# mcu_v2_0_sch.net
KiCad netlist of a schematic drawn in EAGLE
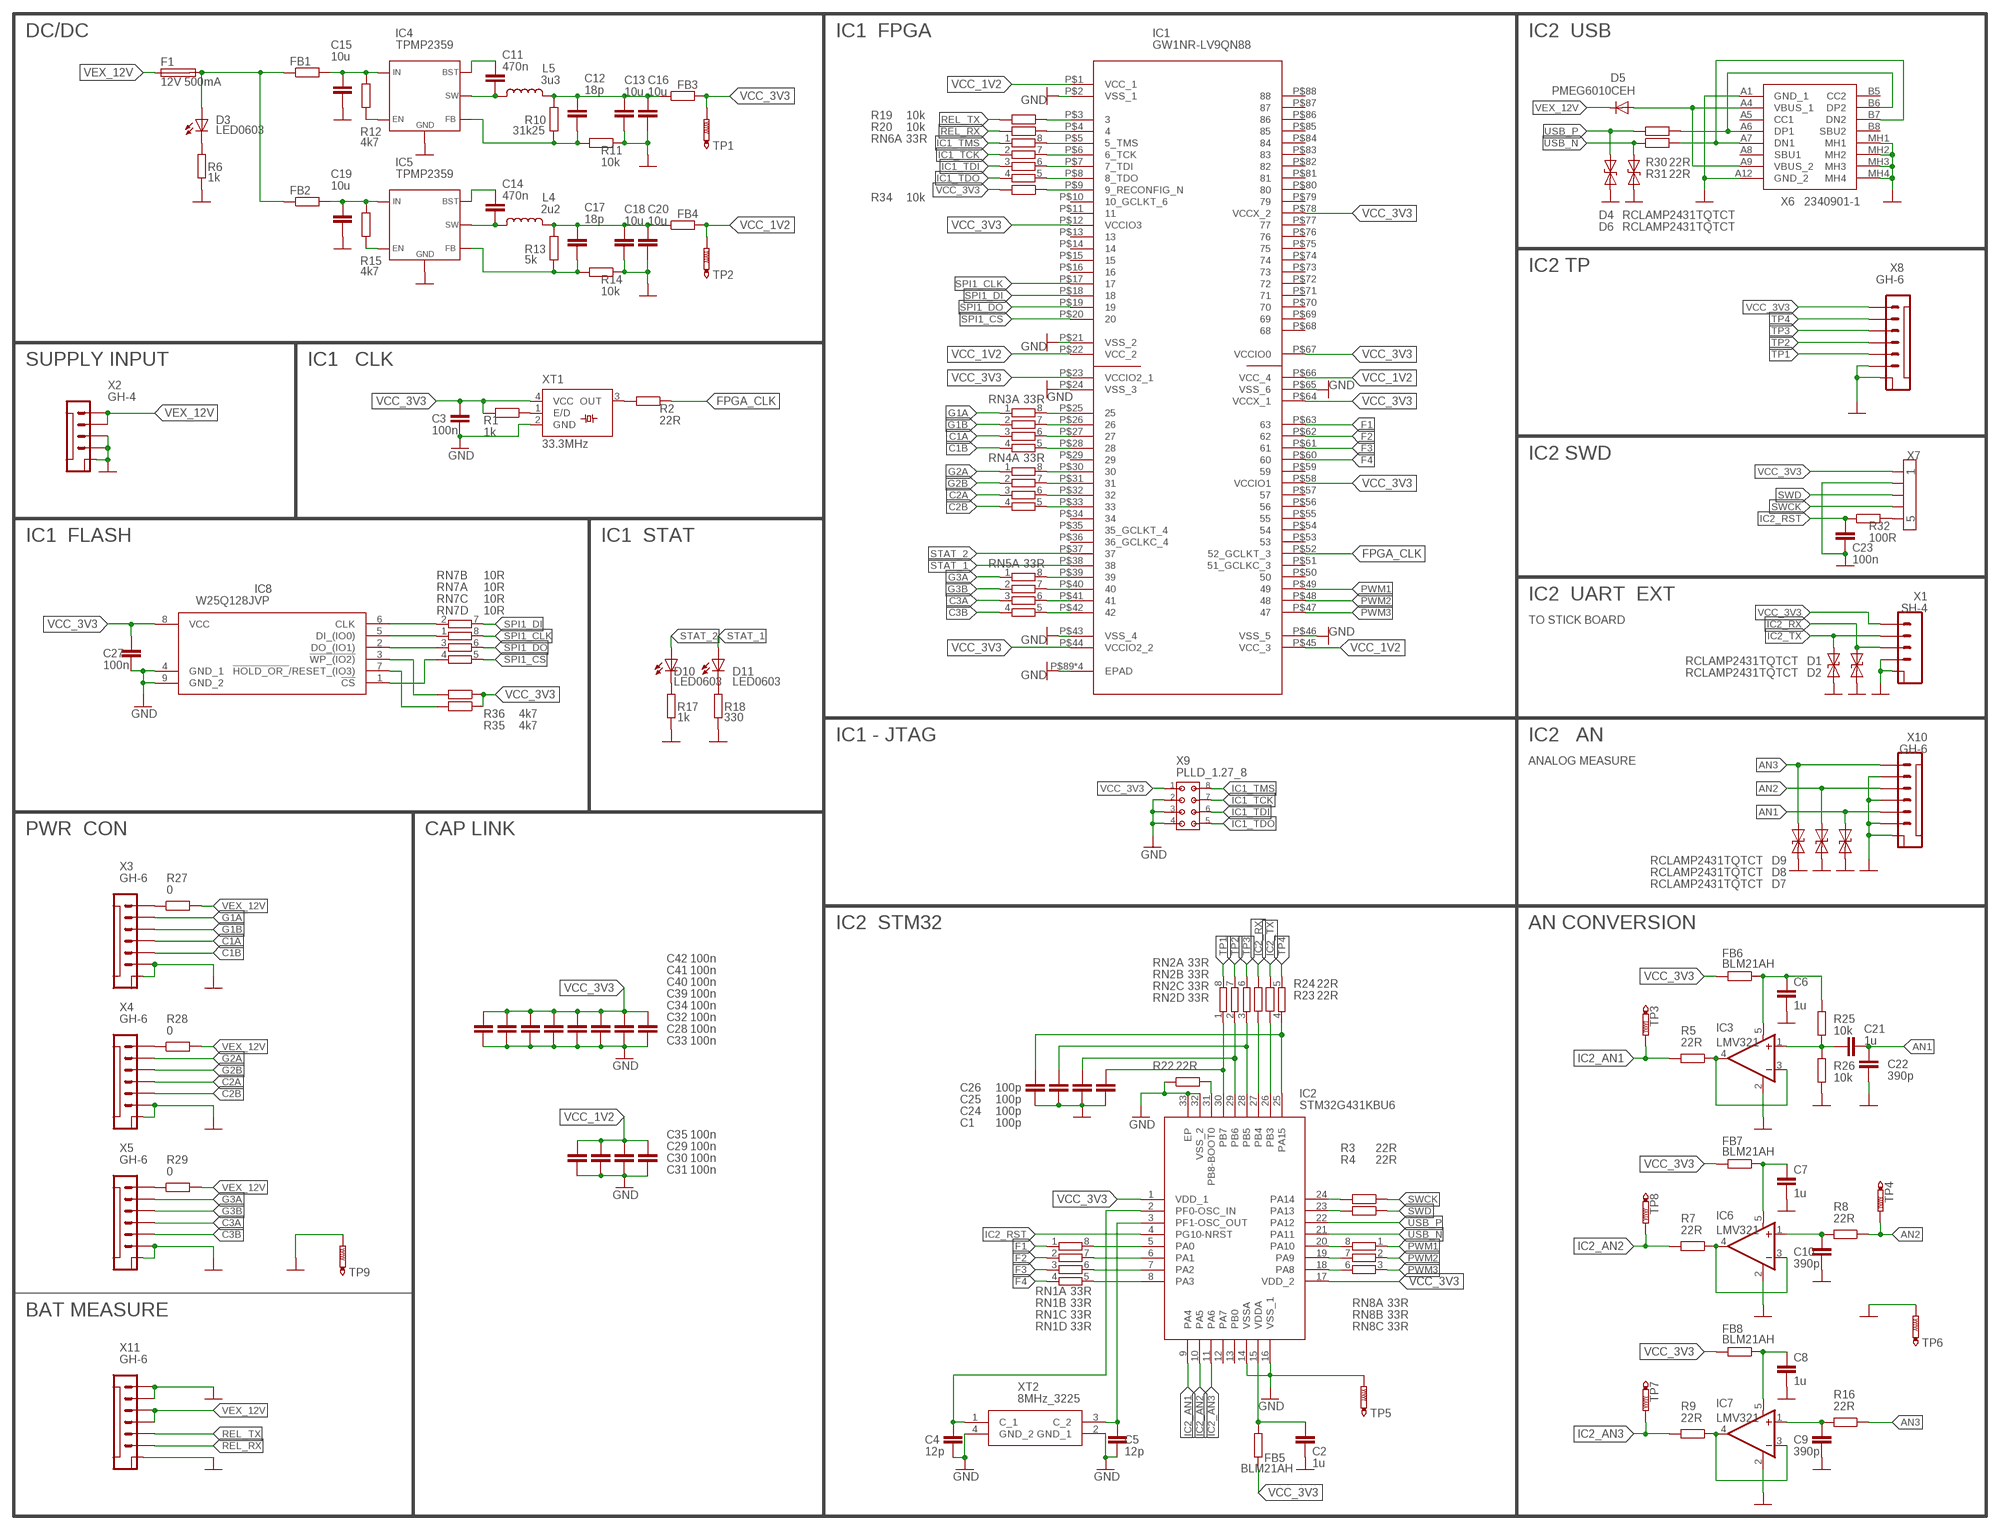
[diagram p0: schematic, sheet 1]

(export (version "E")
  (design (tool "Eeschema 10.0.6"))
  (components
    (comp (ref "C1")
      (value "100p")
      (footprint "eagle-import:C0402")
      (libsource (lib "eagle-import") (part "C-EUC0402"))
    )
    (comp (ref "C2")
      (value "1u")
      (footprint "eagle-import:C0603")
      (libsource (lib "eagle-import") (part "C-EUC0603"))
    )
    (comp (ref "C3")
      (value "100n")
      (footprint "eagle-import:C0603")
      (libsource (lib "eagle-import") (part "C-EUC0603"))
    )
    (comp (ref "C4")
      (value "12p")
      (footprint "eagle-import:C0603")
      (libsource (lib "eagle-import") (part "C-EUC0603"))
    )
    (comp (ref "C5")
      (value "12p")
      (footprint "eagle-import:C0603")
      (libsource (lib "eagle-import") (part "C-EUC0603"))
    )
    (comp (ref "C6")
      (value "1u")
      (footprint "eagle-import:C0603")
      (libsource (lib "eagle-import") (part "C-EUC0603"))
    )
    (comp (ref "C7")
      (value "1u")
      (footprint "eagle-import:C0603")
      (libsource (lib "eagle-import") (part "C-EUC0603"))
    )
    (comp (ref "C8")
      (value "1u")
      (footprint "eagle-import:C0603")
      (libsource (lib "eagle-import") (part "C-EUC0603"))
    )
    (comp (ref "C9")
      (value "390p")
      (footprint "eagle-import:C0603")
      (libsource (lib "eagle-import") (part "C-EUC0603"))
    )
    (comp (ref "C10")
      (value "390p")
      (footprint "eagle-import:C0603")
      (libsource (lib "eagle-import") (part "C-EUC0603"))
    )
    (comp (ref "C11")
      (value "470n")
      (footprint "eagle-import:C0603")
      (libsource (lib "eagle-import") (part "C-EUC0603"))
    )
    (comp (ref "C12")
      (value "18p")
      (footprint "eagle-import:C0603")
      (libsource (lib "eagle-import") (part "C-EUC0603"))
    )
    (comp (ref "C13")
      (value "10u")
      (footprint "eagle-import:C0805")
      (libsource (lib "eagle-import") (part "C-EUC0805"))
    )
    (comp (ref "C14")
      (value "470n")
      (footprint "eagle-import:C0603")
      (libsource (lib "eagle-import") (part "C-EUC0603"))
    )
    (comp (ref "C15")
      (value "10u")
      (footprint "eagle-import:C0805")
      (libsource (lib "eagle-import") (part "C-EUC0805"))
    )
    (comp (ref "C16")
      (value "10u")
      (footprint "eagle-import:C0805")
      (libsource (lib "eagle-import") (part "C-EUC0805"))
    )
    (comp (ref "C17")
      (value "18p")
      (footprint "eagle-import:C0603")
      (libsource (lib "eagle-import") (part "C-EUC0603"))
    )
    (comp (ref "C18")
      (value "10u")
      (footprint "eagle-import:C0805")
      (libsource (lib "eagle-import") (part "C-EUC0805"))
    )
    (comp (ref "C19")
      (value "10u")
      (footprint "eagle-import:C0805")
      (libsource (lib "eagle-import") (part "C-EUC0805"))
    )
    (comp (ref "C20")
      (value "10u")
      (footprint "eagle-import:C0805")
      (libsource (lib "eagle-import") (part "C-EUC0805"))
    )
    (comp (ref "C21")
      (value "1u")
      (footprint "eagle-import:C0603")
      (libsource (lib "eagle-import") (part "C-EUC0603"))
    )
    (comp (ref "C22")
      (value "390p")
      (footprint "eagle-import:C0603")
      (libsource (lib "eagle-import") (part "C-EUC0603"))
    )
    (comp (ref "C23")
      (value "100n")
      (footprint "eagle-import:C0402")
      (libsource (lib "eagle-import") (part "C-EUC0402"))
    )
    (comp (ref "C24")
      (value "100p")
      (footprint "eagle-import:C0402")
      (libsource (lib "eagle-import") (part "C-EUC0402"))
    )
    (comp (ref "C25")
      (value "100p")
      (footprint "eagle-import:C0402")
      (libsource (lib "eagle-import") (part "C-EUC0402"))
    )
    (comp (ref "C26")
      (value "100p")
      (footprint "eagle-import:C0402")
      (libsource (lib "eagle-import") (part "C-EUC0402"))
    )
    (comp (ref "C27")
      (value "100n")
      (footprint "eagle-import:C0603")
      (libsource (lib "eagle-import") (part "C-EUC0603"))
    )
    (comp (ref "C28")
      (value "100n")
      (footprint "eagle-import:C0603")
      (libsource (lib "eagle-import") (part "C-EUC0603"))
    )
    (comp (ref "C29")
      (value "100n")
      (footprint "eagle-import:C0603")
      (libsource (lib "eagle-import") (part "C-EUC0603"))
    )
    (comp (ref "C30")
      (value "100n")
      (footprint "eagle-import:C0603")
      (libsource (lib "eagle-import") (part "C-EUC0603"))
    )
    (comp (ref "C31")
      (value "100n")
      (footprint "eagle-import:C0603")
      (libsource (lib "eagle-import") (part "C-EUC0603"))
    )
    (comp (ref "C32")
      (value "100n")
      (footprint "eagle-import:C0603")
      (libsource (lib "eagle-import") (part "C-EUC0603"))
    )
    (comp (ref "C33")
      (value "100n")
      (footprint "eagle-import:C0603")
      (libsource (lib "eagle-import") (part "C-EUC0603"))
    )
    (comp (ref "C34")
      (value "100n")
      (footprint "eagle-import:C0603")
      (libsource (lib "eagle-import") (part "C-EUC0603"))
    )
    (comp (ref "C35")
      (value "100n")
      (footprint "eagle-import:C0603")
      (libsource (lib "eagle-import") (part "C-EUC0603"))
    )
    (comp (ref "C39")
      (value "100n")
      (footprint "eagle-import:C0603")
      (libsource (lib "eagle-import") (part "C-EUC0603"))
    )
    (comp (ref "C40")
      (value "100n")
      (footprint "eagle-import:C0603")
      (libsource (lib "eagle-import") (part "C-EUC0603"))
    )
    (comp (ref "C41")
      (value "100n")
      (footprint "eagle-import:C0603")
      (libsource (lib "eagle-import") (part "C-EUC0603"))
    )
    (comp (ref "C42")
      (value "100n")
      (footprint "eagle-import:C0603")
      (libsource (lib "eagle-import") (part "C-EUC0603"))
    )
    (comp (ref "D1")
      (value "RCLAMP2431TQTCT")
      (footprint "eagle-import:RCLAMP2431TQTCT")
      (fields (field (name "MOUSER_PART_NUMBER") "947-RCLAMP2431TQTCT"))
      (libsource (lib "eagle-import") (part "RCLAMP2431TQTCT"))
    )
    (comp (ref "D2")
      (value "RCLAMP2431TQTCT")
      (footprint "eagle-import:RCLAMP2431TQTCT")
      (fields (field (name "MOUSER_PART_NUMBER") "947-RCLAMP2431TQTCT"))
      (libsource (lib "eagle-import") (part "RCLAMP2431TQTCT"))
    )
    (comp (ref "D3")
      (value "LED0603")
      (footprint "eagle-import:SML0603")
      (libsource (lib "eagle-import") (part "LED0603"))
    )
    (comp (ref "D4")
      (value "RCLAMP2431TQTCT")
      (footprint "eagle-import:RCLAMP2431TQTCT")
      (fields (field (name "MOUSER_PART_NUMBER") "947-RCLAMP2431TQTCT"))
      (libsource (lib "eagle-import") (part "RCLAMP2431TQTCT"))
    )
    (comp (ref "D5")
      (value "PMEG6010CEH")
      (footprint "eagle-import:SOD123")
      (libsource (lib "eagle-import") (part "PMEG6010CEH"))
    )
    (comp (ref "D6")
      (value "RCLAMP2431TQTCT")
      (footprint "eagle-import:RCLAMP2431TQTCT")
      (fields (field (name "MOUSER_PART_NUMBER") "947-RCLAMP2431TQTCT"))
      (libsource (lib "eagle-import") (part "RCLAMP2431TQTCT"))
    )
    (comp (ref "D7")
      (value "RCLAMP2431TQTCT")
      (footprint "eagle-import:RCLAMP2431TQTCT")
      (fields (field (name "MOUSER_PART_NUMBER") "947-RCLAMP2431TQTCT"))
      (libsource (lib "eagle-import") (part "RCLAMP2431TQTCT"))
    )
    (comp (ref "D8")
      (value "RCLAMP2431TQTCT")
      (footprint "eagle-import:RCLAMP2431TQTCT")
      (fields (field (name "MOUSER_PART_NUMBER") "947-RCLAMP2431TQTCT"))
      (libsource (lib "eagle-import") (part "RCLAMP2431TQTCT"))
    )
    (comp (ref "D9")
      (value "RCLAMP2431TQTCT")
      (footprint "eagle-import:RCLAMP2431TQTCT")
      (fields (field (name "MOUSER_PART_NUMBER") "947-RCLAMP2431TQTCT"))
      (libsource (lib "eagle-import") (part "RCLAMP2431TQTCT"))
    )
    (comp (ref "D10")
      (value "LED0603")
      (footprint "eagle-import:SML0603")
      (libsource (lib "eagle-import") (part "LED0603"))
    )
    (comp (ref "D11")
      (value "LED0603")
      (footprint "eagle-import:SML0603")
      (libsource (lib "eagle-import") (part "LED0603"))
    )
    (comp (ref "F1")
      (value "12V 500mA")
      (footprint "eagle-import:MF-MSMF050")
      (libsource (lib "eagle-import") (part "MF-MSMF"))
    )
    (comp (ref "FB1")
      (value "R-EU_R0805")
      (footprint "eagle-import:R0805")
      (libsource (lib "eagle-import") (part "R-EU_R0805"))
    )
    (comp (ref "FB2")
      (value "R-EU_R0805")
      (footprint "eagle-import:R0805")
      (libsource (lib "eagle-import") (part "R-EU_R0805"))
    )
    (comp (ref "FB3")
      (value "R-EU_R0805")
      (footprint "eagle-import:R0805")
      (libsource (lib "eagle-import") (part "R-EU_R0805"))
    )
    (comp (ref "FB4")
      (value "R-EU_R0805")
      (footprint "eagle-import:R0805")
      (libsource (lib "eagle-import") (part "R-EU_R0805"))
    )
    (comp (ref "FB5")
      (value "BLM21AH")
      (footprint "eagle-import:R0805")
      (libsource (lib "eagle-import") (part "R-EU_R0805"))
    )
    (comp (ref "FB6")
      (value "BLM21AH")
      (footprint "eagle-import:R0805")
      (libsource (lib "eagle-import") (part "R-EU_R0805"))
    )
    (comp (ref "FB7")
      (value "BLM21AH")
      (footprint "eagle-import:R0805")
      (libsource (lib "eagle-import") (part "R-EU_R0805"))
    )
    (comp (ref "FB8")
      (value "BLM21AH")
      (footprint "eagle-import:R0805")
      (libsource (lib "eagle-import") (part "R-EU_R0805"))
    )
    (comp (ref "IC1")
      (value "GW1NR-LV9QN88")
      (footprint "eagle-import:QFN88")
      (libsource (lib "eagle-import") (part "GW1NR-LV9QN88"))
    )
    (comp (ref "IC2")
      (value "STM32G431KBU6")
      (footprint "eagle-import:QFN50P500X500X60-33N")
      (fields (field (name "MOUSER_PART_NUMBER") "511-STM32G431KBU6"))
      (libsource (lib "eagle-import") (part "STM32G431KBU6"))
    )
    (comp (ref "IC3")
      (value "LMV321")
      (footprint "eagle-import:SOT23-5")
      (libsource (lib "eagle-import") (part "LMV321"))
    )
    (comp (ref "IC4")
      (value "TPMP2359")
      (footprint "eagle-import:SOT-23-6")
      (libsource (lib "eagle-import") (part "MP2359"))
    )
    (comp (ref "IC5")
      (value "TPMP2359")
      (footprint "eagle-import:SOT-23-6")
      (libsource (lib "eagle-import") (part "MP2359"))
    )
    (comp (ref "IC6")
      (value "LMV321")
      (footprint "eagle-import:SOT23-5")
      (libsource (lib "eagle-import") (part "LMV321"))
    )
    (comp (ref "IC7")
      (value "LMV321")
      (footprint "eagle-import:SOT23-5")
      (libsource (lib "eagle-import") (part "LMV321"))
    )
    (comp (ref "IC8")
      (value "W25Q128JVP")
      (footprint "eagle-import:WSON-8(5X6)")
      (fields
        (field (name "ARROW_PART_NUMBER") "W25Q128JVPIQ")
        (field (name "MOUSER_PART_NUMBER") "454-W25Q128JVPIQ")
      )
      (libsource (lib "eagle-import") (part "W25Q128JVPIQWSON-8(5X6)"))
    )
    (comp (ref "L4")
      (value "2u2")
      (footprint "eagle-import:SRN3015")
      (libsource (lib "eagle-import") (part "SRN3015"))
    )
    (comp (ref "L5")
      (value "3u3")
      (footprint "eagle-import:SRN3015")
      (libsource (lib "eagle-import") (part "SRN3015"))
    )
    (comp (ref "R1")
      (value "1k")
      (footprint "eagle-import:R0603")
      (libsource (lib "eagle-import") (part "R-EU_R0603"))
    )
    (comp (ref "R2")
      (value "22R")
      (footprint "eagle-import:R0603")
      (libsource (lib "eagle-import") (part "R-EU_R0603"))
    )
    (comp (ref "R3")
      (value "22R")
      (footprint "eagle-import:R0402")
      (libsource (lib "eagle-import") (part "R-EU_R0402"))
    )
    (comp (ref "R4")
      (value "22R")
      (footprint "eagle-import:R0402")
      (libsource (lib "eagle-import") (part "R-EU_R0402"))
    )
    (comp (ref "R5")
      (value "22R")
      (footprint "eagle-import:R0603")
      (libsource (lib "eagle-import") (part "R-EU_R0603"))
    )
    (comp (ref "R6")
      (value "1k")
      (footprint "eagle-import:R0603")
      (libsource (lib "eagle-import") (part "R-EU_R0603"))
    )
    (comp (ref "R7")
      (value "22R")
      (footprint "eagle-import:R0603")
      (libsource (lib "eagle-import") (part "R-EU_R0603"))
    )
    (comp (ref "R8")
      (value "22R")
      (footprint "eagle-import:R0603")
      (libsource (lib "eagle-import") (part "R-EU_R0603"))
    )
    (comp (ref "R9")
      (value "22R")
      (footprint "eagle-import:R0603")
      (libsource (lib "eagle-import") (part "R-EU_R0603"))
    )
    (comp (ref "R10")
      (value "31k25")
      (footprint "eagle-import:R0603")
      (libsource (lib "eagle-import") (part "R-EU_R0603"))
    )
    (comp (ref "R11")
      (value "10k")
      (footprint "eagle-import:R0402")
      (libsource (lib "eagle-import") (part "R-EU_R0402"))
    )
    (comp (ref "R12")
      (value "4k7")
      (footprint "eagle-import:R0402")
      (libsource (lib "eagle-import") (part "R-EU_R0402"))
    )
    (comp (ref "R13")
      (value "5k")
      (footprint "eagle-import:R0603")
      (libsource (lib "eagle-import") (part "R-EU_R0603"))
    )
    (comp (ref "R14")
      (value "10k")
      (footprint "eagle-import:R0402")
      (libsource (lib "eagle-import") (part "R-EU_R0402"))
    )
    (comp (ref "R15")
      (value "4k7")
      (footprint "eagle-import:R0402")
      (libsource (lib "eagle-import") (part "R-EU_R0402"))
    )
    (comp (ref "R16")
      (value "22R")
      (footprint "eagle-import:R0603")
      (libsource (lib "eagle-import") (part "R-EU_R0603"))
    )
    (comp (ref "R17")
      (value "1k")
      (footprint "eagle-import:R0603")
      (libsource (lib "eagle-import") (part "R-EU_R0603"))
    )
    (comp (ref "R18")
      (value "330")
      (footprint "eagle-import:R0603")
      (libsource (lib "eagle-import") (part "R-EU_R0603"))
    )
    (comp (ref "R19")
      (value "10k")
      (footprint "eagle-import:R0402")
      (libsource (lib "eagle-import") (part "R-EU_R0402"))
    )
    (comp (ref "R20")
      (value "10k")
      (footprint "eagle-import:R0402")
      (libsource (lib "eagle-import") (part "R-EU_R0402"))
    )
    (comp (ref "R22")
      (value "22R")
      (footprint "eagle-import:R0402")
      (libsource (lib "eagle-import") (part "R-EU_R0402"))
    )
    (comp (ref "R23")
      (value "22R")
      (footprint "eagle-import:R0603")
      (libsource (lib "eagle-import") (part "R-EU_R0603"))
    )
    (comp (ref "R24")
      (value "22R")
      (footprint "eagle-import:R0603")
      (libsource (lib "eagle-import") (part "R-EU_R0603"))
    )
    (comp (ref "R25")
      (value "10k")
      (footprint "eagle-import:R0603")
      (libsource (lib "eagle-import") (part "R-EU_R0603"))
    )
    (comp (ref "R26")
      (value "10k")
      (footprint "eagle-import:R0603")
      (libsource (lib "eagle-import") (part "R-EU_R0603"))
    )
    (comp (ref "R27")
      (value "0")
      (footprint "eagle-import:R1206")
      (libsource (lib "eagle-import") (part "R-EU_R1206"))
    )
    (comp (ref "R28")
      (value "0")
      (footprint "eagle-import:R1206")
      (libsource (lib "eagle-import") (part "R-EU_R1206"))
    )
    (comp (ref "R29")
      (value "0")
      (footprint "eagle-import:R1206")
      (libsource (lib "eagle-import") (part "R-EU_R1206"))
    )
    (comp (ref "R30")
      (value "22R")
      (footprint "eagle-import:R0603")
      (libsource (lib "eagle-import") (part "R-EU_R0603"))
    )
    (comp (ref "R31")
      (value "22R")
      (footprint "eagle-import:R0603")
      (libsource (lib "eagle-import") (part "R-EU_R0603"))
    )
    (comp (ref "R32")
      (value "100R")
      (footprint "eagle-import:R0402")
      (libsource (lib "eagle-import") (part "R-EU_R0402"))
    )
    (comp (ref "R34")
      (value "10k")
      (footprint "eagle-import:R0603")
      (libsource (lib "eagle-import") (part "R-EU_R0603"))
    )
    (comp (ref "R35")
      (value "4k7")
      (footprint "eagle-import:R0603")
      (libsource (lib "eagle-import") (part "R-EU_R0603"))
    )
    (comp (ref "R36")
      (value "4k7")
      (footprint "eagle-import:R0603")
      (libsource (lib "eagle-import") (part "R-EU_R0603"))
    )
    (comp (ref "RN1")
      (value "33R")
      (footprint "eagle-import:0603-ARC")
      (libsource (lib "eagle-import") (part "4R-N0603-ARC"))
    )
    (comp (ref "RN2")
      (value "33R")
      (footprint "eagle-import:0603-ARC")
      (libsource (lib "eagle-import") (part "4R-N0603-ARC"))
    )
    (comp (ref "RN3")
      (value "33R")
      (footprint "eagle-import:0603-ARC")
      (libsource (lib "eagle-import") (part "4R-N0603-ARC"))
    )
    (comp (ref "RN4")
      (value "33R")
      (footprint "eagle-import:0603-ARC")
      (libsource (lib "eagle-import") (part "4R-N0603-ARC"))
    )
    (comp (ref "RN5")
      (value "33R")
      (footprint "eagle-import:0603-ARC")
      (libsource (lib "eagle-import") (part "4R-N0603-ARC"))
    )
    (comp (ref "RN6")
      (value "33R")
      (footprint "eagle-import:0603-ARC")
      (libsource (lib "eagle-import") (part "4R-N0603-ARC"))
    )
    (comp (ref "RN7")
      (value "10R")
      (footprint "eagle-import:0603-ARC")
      (libsource (lib "eagle-import") (part "4R-N0603-ARC"))
    )
    (comp (ref "RN8")
      (value "33R")
      (footprint "eagle-import:0603-ARC")
      (libsource (lib "eagle-import") (part "4R-N0603-ARC"))
    )
    (comp (ref "TP1")
      (value "PTR1B1,27")
      (footprint "eagle-import:B1,27")
      (libsource (lib "eagle-import") (part "PTR1B1,27"))
    )
    (comp (ref "TP2")
      (value "PTR1B1,27")
      (footprint "eagle-import:B1,27")
      (libsource (lib "eagle-import") (part "PTR1B1,27"))
    )
    (comp (ref "TP3")
      (value "PTR1B1,27")
      (footprint "eagle-import:B1,27")
      (libsource (lib "eagle-import") (part "PTR1B1,27"))
    )
    (comp (ref "TP4")
      (value "PTR1B1,27")
      (footprint "eagle-import:B1,27")
      (libsource (lib "eagle-import") (part "PTR1B1,27"))
    )
    (comp (ref "TP5")
      (value "PTR1B1,27")
      (footprint "eagle-import:B1,27")
      (libsource (lib "eagle-import") (part "PTR1B1,27"))
    )
    (comp (ref "TP6")
      (value "PTR1B1,27")
      (footprint "eagle-import:B1,27")
      (libsource (lib "eagle-import") (part "PTR1B1,27"))
    )
    (comp (ref "TP7")
      (value "PTR1B1,27")
      (footprint "eagle-import:B1,27")
      (libsource (lib "eagle-import") (part "PTR1B1,27"))
    )
    (comp (ref "TP8")
      (value "PTR1B1,27")
      (footprint "eagle-import:B1,27")
      (libsource (lib "eagle-import") (part "PTR1B1,27"))
    )
    (comp (ref "TP9")
      (value "PTR1B1,27")
      (footprint "eagle-import:B1,27")
      (libsource (lib "eagle-import") (part "PTR1B1,27"))
    )
    (comp (ref "X1")
      (value "SH-4")
      (footprint "eagle-import:SH-4")
      (libsource (lib "eagle-import") (part "SH-4"))
    )
    (comp (ref "X2")
      (value "GH-4")
      (footprint "eagle-import:GH-4-H")
      (libsource (lib "eagle-import") (part "GH-4"))
    )
    (comp (ref "X3")
      (value "GH-6")
      (footprint "eagle-import:GH-6")
      (libsource (lib "eagle-import") (part "GH-6"))
    )
    (comp (ref "X4")
      (value "GH-6")
      (footprint "eagle-import:GH-6")
      (libsource (lib "eagle-import") (part "GH-6"))
    )
    (comp (ref "X5")
      (value "GH-6")
      (footprint "eagle-import:GH-6")
      (libsource (lib "eagle-import") (part "GH-6"))
    )
    (comp (ref "X6")
      (value "2340901-1")
      (footprint "eagle-import:23409011")
      (fields (field (name "MOUSER_PART_NUMBER") "571-2340901-1"))
      (libsource (lib "eagle-import") (part "2340901-1"))
    )
    (comp (ref "X7")
      (value "PIN_HEADER_1.27_5")
      (footprint "eagle-import:PIN_HEADER_1.27_5")
      (libsource (lib "eagle-import") (part "PIN_HEADER_1.27_5"))
    )
    (comp (ref "X8")
      (value "GH-6")
      (footprint "eagle-import:GH-6")
      (libsource (lib "eagle-import") (part "GH-6"))
    )
    (comp (ref "X9")
      (value "PLLD_1.27_8")
      (footprint "eagle-import:PLD_1.27_8")
      (libsource (lib "eagle-import") (part "PLLD_1.27_8"))
    )
    (comp (ref "X10")
      (value "GH-6")
      (footprint "eagle-import:GH-6")
      (libsource (lib "eagle-import") (part "GH-6"))
    )
    (comp (ref "X11")
      (value "GH-6")
      (footprint "eagle-import:GH-6")
      (libsource (lib "eagle-import") (part "GH-6"))
    )
    (comp (ref "XT1")
      (value "33.3MHz")
      (footprint "eagle-import:3.2X2.5MM")
      (libsource (lib "eagle-import") (part "LFXTAL"))
    )
    (comp (ref "XT2")
      (value "8MHz_3225")
      (footprint "eagle-import:3.2X2.5MM")
      (libsource (lib "eagle-import") (part "CRYSTAL_3225"))
    )
  )
  (nets
    (net (code "1") (name "AN1") (class "Default")
      (node (ref "C21") (pin "2") (pinfunction "2_2") (pintype "passive"))
      (node (ref "C22") (pin "1") (pinfunction "1_1") (pintype "passive"))
      (node (ref "D7") (pin "1") (pinfunction "A_1") (pintype "passive"))
      (node (ref "X10") (pin "P$5") (pinfunction "5_P$5") (pintype "passive"))
    )
    (net (code "2") (name "AN2") (class "Default")
      (node (ref "D8") (pin "1") (pinfunction "A_1") (pintype "passive"))
      (node (ref "R8") (pin "1") (pinfunction "1_1") (pintype "passive"))
      (node (ref "TP4") (pin "TP") (pinfunction "TP_TP") (pintype "input"))
      (node (ref "X10") (pin "P$3") (pinfunction "3_P$3") (pintype "passive"))
    )
    (net (code "3") (name "AN3") (class "Default")
      (node (ref "D9") (pin "1") (pinfunction "A_1") (pintype "passive"))
      (node (ref "R16") (pin "1") (pinfunction "1_1") (pintype "passive"))
      (node (ref "X10") (pin "P$1") (pinfunction "1_P$1") (pintype "passive"))
    )
    (net (code "4") (name "C1A") (class "Default")
      (node (ref "RN3") (pin "3") (pinfunction "1_3") (pintype "passive"))
      (node (ref "X3") (pin "P$4") (pinfunction "4_P$4") (pintype "passive"))
    )
    (net (code "5") (name "C1B") (class "Default")
      (node (ref "RN3") (pin "4") (pinfunction "1_4") (pintype "passive"))
      (node (ref "X3") (pin "P$5") (pinfunction "5_P$5") (pintype "passive"))
    )
    (net (code "6") (name "C2A") (class "Default")
      (node (ref "RN4") (pin "3") (pinfunction "1_3") (pintype "passive"))
      (node (ref "X4") (pin "P$4") (pinfunction "4_P$4") (pintype "passive"))
    )
    (net (code "7") (name "C2B") (class "Default")
      (node (ref "RN4") (pin "4") (pinfunction "1_4") (pintype "passive"))
      (node (ref "X4") (pin "P$5") (pinfunction "5_P$5") (pintype "passive"))
    )
    (net (code "8") (name "C3A") (class "Default")
      (node (ref "RN5") (pin "3") (pinfunction "1_3") (pintype "passive"))
      (node (ref "X5") (pin "P$4") (pinfunction "4_P$4") (pintype "passive"))
    )
    (net (code "9") (name "C3B") (class "Default")
      (node (ref "RN5") (pin "4") (pinfunction "1_4") (pintype "passive"))
      (node (ref "X5") (pin "P$5") (pinfunction "5_P$5") (pintype "passive"))
    )
    (net (code "10") (name "F1") (class "Default")
      (node (ref "IC1") (pin "P$63") (pinfunction "63_P$63") (pintype "bidirectional"))
      (node (ref "RN1") (pin "1") (pinfunction "1_1") (pintype "passive"))
    )
    (net (code "11") (name "F2") (class "Default")
      (node (ref "IC1") (pin "P$62") (pinfunction "62_P$62") (pintype "bidirectional"))
      (node (ref "RN1") (pin "2") (pinfunction "1_2") (pintype "passive"))
    )
    (net (code "12") (name "F3") (class "Default")
      (node (ref "IC1") (pin "P$61") (pinfunction "61_P$61") (pintype "bidirectional"))
      (node (ref "RN1") (pin "3") (pinfunction "1_3") (pintype "passive"))
    )
    (net (code "13") (name "F4") (class "Default")
      (node (ref "IC1") (pin "P$60") (pinfunction "60_P$60") (pintype "bidirectional"))
      (node (ref "RN1") (pin "4") (pinfunction "1_4") (pintype "passive"))
    )
    (net (code "14") (name "FPGA_CLK") (class "Default")
      (node (ref "IC1") (pin "P$52") (pinfunction "52_GCLKT_3_P$52") (pintype "bidirectional"))
      (node (ref "R2") (pin "1") (pinfunction "1_1") (pintype "passive"))
    )
    (net (code "15") (name "G1A") (class "Default")
      (node (ref "RN3") (pin "1") (pinfunction "1_1") (pintype "passive"))
      (node (ref "X3") (pin "P$2") (pinfunction "2_P$2") (pintype "passive"))
    )
    (net (code "16") (name "G1B") (class "Default")
      (node (ref "RN3") (pin "2") (pinfunction "1_2") (pintype "passive"))
      (node (ref "X3") (pin "P$3") (pinfunction "3_P$3") (pintype "passive"))
    )
    (net (code "17") (name "G2A") (class "Default")
      (node (ref "RN4") (pin "1") (pinfunction "1_1") (pintype "passive"))
      (node (ref "X4") (pin "P$2") (pinfunction "2_P$2") (pintype "passive"))
    )
    (net (code "18") (name "G2B") (class "Default")
      (node (ref "RN4") (pin "2") (pinfunction "1_2") (pintype "passive"))
      (node (ref "X4") (pin "P$3") (pinfunction "3_P$3") (pintype "passive"))
    )
    (net (code "19") (name "G3A") (class "Default")
      (node (ref "RN5") (pin "1") (pinfunction "1_1") (pintype "passive"))
      (node (ref "X5") (pin "P$2") (pinfunction "2_P$2") (pintype "passive"))
    )
    (net (code "20") (name "G3B") (class "Default")
      (node (ref "RN5") (pin "2") (pinfunction "1_2") (pintype "passive"))
      (node (ref "X5") (pin "P$3") (pinfunction "3_P$3") (pintype "passive"))
    )
    (net (code "21") (name "GND") (class "Default")
      (node (ref "C1") (pin "1") (pinfunction "1_1") (pintype "passive"))
      (node (ref "C10") (pin "2") (pinfunction "2_2") (pintype "passive"))
      (node (ref "C13") (pin "2") (pinfunction "2_2") (pintype "passive"))
      (node (ref "C15") (pin "2") (pinfunction "2_2") (pintype "passive"))
      (node (ref "C16") (pin "2") (pinfunction "2_2") (pintype "passive"))
      (node (ref "C18") (pin "2") (pinfunction "2_2") (pintype "passive"))
      (node (ref "C19") (pin "2") (pinfunction "2_2") (pintype "passive"))
      (node (ref "C2") (pin "2") (pinfunction "2_2") (pintype "passive"))
      (node (ref "C20") (pin "2") (pinfunction "2_2") (pintype "passive"))
      (node (ref "C22") (pin "2") (pinfunction "2_2") (pintype "passive"))
      (node (ref "C23") (pin "1") (pinfunction "1_1") (pintype "passive"))
      (node (ref "C24") (pin "1") (pinfunction "1_1") (pintype "passive"))
      (node (ref "C25") (pin "1") (pinfunction "1_1") (pintype "passive"))
      (node (ref "C26") (pin "1") (pinfunction "1_1") (pintype "passive"))
      (node (ref "C27") (pin "2") (pinfunction "2_2") (pintype "passive"))
      (node (ref "C28") (pin "2") (pinfunction "2_2") (pintype "passive"))
      (node (ref "C29") (pin "2") (pinfunction "2_2") (pintype "passive"))
      (node (ref "C3") (pin "2") (pinfunction "2_2") (pintype "passive"))
      (node (ref "C30") (pin "2") (pinfunction "2_2") (pintype "passive"))
      (node (ref "C31") (pin "2") (pinfunction "2_2") (pintype "passive"))
      (node (ref "C32") (pin "2") (pinfunction "2_2") (pintype "passive"))
      (node (ref "C33") (pin "2") (pinfunction "2_2") (pintype "passive"))
      (node (ref "C34") (pin "2") (pinfunction "2_2") (pintype "passive"))
      (node (ref "C35") (pin "2") (pinfunction "2_2") (pintype "passive"))
      (node (ref "C39") (pin "2") (pinfunction "2_2") (pintype "passive"))
      (node (ref "C4") (pin "2") (pinfunction "2_2") (pintype "passive"))
      (node (ref "C40") (pin "2") (pinfunction "2_2") (pintype "passive"))
      (node (ref "C41") (pin "2") (pinfunction "2_2") (pintype "passive"))
      (node (ref "C42") (pin "2") (pinfunction "2_2") (pintype "passive"))
      (node (ref "C5") (pin "2") (pinfunction "2_2") (pintype "passive"))
      (node (ref "C6") (pin "2") (pinfunction "2_2") (pintype "passive"))
      (node (ref "C7") (pin "2") (pinfunction "2_2") (pintype "passive"))
      (node (ref "C8") (pin "2") (pinfunction "2_2") (pintype "passive"))
      (node (ref "C9") (pin "2") (pinfunction "2_2") (pintype "passive"))
      (node (ref "D1") (pin "2") (pinfunction "A1_2") (pintype "passive"))
      (node (ref "D2") (pin "2") (pinfunction "A1_2") (pintype "passive"))
      (node (ref "D4") (pin "2") (pinfunction "A1_2") (pintype "passive"))
      (node (ref "D6") (pin "2") (pinfunction "A1_2") (pintype "passive"))
      (node (ref "D7") (pin "2") (pinfunction "A1_2") (pintype "passive"))
      (node (ref "D8") (pin "2") (pinfunction "A1_2") (pintype "passive"))
      (node (ref "D9") (pin "2") (pinfunction "A1_2") (pintype "passive"))
      (node (ref "IC1") (pin "P$2") (pinfunction "VSS_1_P$2") (pintype "bidirectional"))
      (node (ref "IC1") (pin "P$21") (pinfunction "VSS_2_P$21") (pintype "bidirectional"))
      (node (ref "IC1") (pin "P$24") (pinfunction "VSS_3_P$24") (pintype "bidirectional"))
      (node (ref "IC1") (pin "P$43") (pinfunction "VSS_4_P$43") (pintype "bidirectional"))
      (node (ref "IC1") (pin "P$46") (pinfunction "VSS_5_P$46") (pintype "bidirectional"))
      (node (ref "IC1") (pin "P$65") (pinfunction "VSS_6_P$65") (pintype "bidirectional"))
      (node (ref "IC1") (pin "P$89") (pinfunction "EPAD_P$89") (pintype "bidirectional"))
      (node (ref "IC1") (pin "P$90") (pinfunction "EPAD_P$90") (pintype "bidirectional"))
      (node (ref "IC1") (pin "P$91") (pinfunction "EPAD_P$91") (pintype "bidirectional"))
      (node (ref "IC1") (pin "P$92") (pinfunction "EPAD_P$92") (pintype "bidirectional"))
      (node (ref "IC2") (pin "14") (pinfunction "VSSA_14") (pintype "bidirectional"))
      (node (ref "IC2") (pin "16") (pinfunction "VSS_1_16") (pintype "bidirectional"))
      (node (ref "IC2") (pin "32") (pinfunction "VSS_2_32") (pintype "bidirectional"))
      (node (ref "IC2") (pin "33") (pinfunction "EP_33") (pintype "bidirectional"))
      (node (ref "IC3") (pin "2") (pinfunction "V-_2") (pintype "power_in"))
      (node (ref "IC4") (pin "2") (pinfunction "GND_2") (pintype "bidirectional"))
      (node (ref "IC5") (pin "2") (pinfunction "GND_2") (pintype "bidirectional"))
      (node (ref "IC6") (pin "2") (pinfunction "V-_2") (pintype "power_in"))
      (node (ref "IC7") (pin "2") (pinfunction "V-_2") (pintype "power_in"))
      (node (ref "IC8") (pin "4") (pinfunction "GND_1_4") (pintype "bidirectional"))
      (node (ref "IC8") (pin "9") (pinfunction "GND_2_9") (pintype "bidirectional"))
      (node (ref "R11") (pin "1") (pinfunction "1_1") (pintype "passive"))
      (node (ref "R14") (pin "1") (pinfunction "1_1") (pintype "passive"))
      (node (ref "R17") (pin "1") (pinfunction "1_1") (pintype "passive"))
      (node (ref "R18") (pin "1") (pinfunction "1_1") (pintype "passive"))
      (node (ref "R22") (pin "1") (pinfunction "1_1") (pintype "passive"))
      (node (ref "R26") (pin "2") (pinfunction "2_2") (pintype "passive"))
      (node (ref "R6") (pin "1") (pinfunction "1_1") (pintype "passive"))
      (node (ref "TP5") (pin "TP") (pinfunction "TP_TP") (pintype "input"))
      (node (ref "TP6") (pin "TP") (pinfunction "TP_TP") (pintype "input"))
      (node (ref "TP9") (pin "TP") (pinfunction "TP_TP") (pintype "input"))
      (node (ref "X1") (pin "G1") (pinfunction "G_G1") (pintype "bidirectional"))
      (node (ref "X1") (pin "G2") (pinfunction "G_G2") (pintype "bidirectional"))
      (node (ref "X1") (pin "P$4") (pinfunction "4_P$4") (pintype "passive"))
      (node (ref "X10") (pin "P$2") (pinfunction "2_P$2") (pintype "passive"))
      (node (ref "X10") (pin "P$4") (pinfunction "4_P$4") (pintype "passive"))
      (node (ref "X10") (pin "P$6") (pinfunction "6_P$6") (pintype "passive"))
      (node (ref "X10") (pin "P$7") (pinfunction "G_P$7") (pintype "bidirectional"))
      (node (ref "X10") (pin "P$8") (pinfunction "G_P$8") (pintype "bidirectional"))
      (node (ref "X11") (pin "P$1") (pinfunction "1_P$1") (pintype "passive"))
      (node (ref "X11") (pin "P$2") (pinfunction "2_P$2") (pintype "passive"))
      (node (ref "X11") (pin "P$7") (pinfunction "G_P$7") (pintype "bidirectional"))
      (node (ref "X11") (pin "P$8") (pinfunction "G_P$8") (pintype "bidirectional"))
      (node (ref "X2") (pin "3") (pinfunction "3_3") (pintype "passive"))
      (node (ref "X2") (pin "4") (pinfunction "4_4") (pintype "passive"))
      (node (ref "X2") (pin "P$7") (pinfunction "G_P$7") (pintype "bidirectional"))
      (node (ref "X2") (pin "P$8") (pinfunction "G_P$8") (pintype "bidirectional"))
      (node (ref "X3") (pin "P$6") (pinfunction "6_P$6") (pintype "passive"))
      (node (ref "X3") (pin "P$7") (pinfunction "G_P$7") (pintype "bidirectional"))
      (node (ref "X3") (pin "P$8") (pinfunction "G_P$8") (pintype "bidirectional"))
      (node (ref "X4") (pin "P$6") (pinfunction "6_P$6") (pintype "passive"))
      (node (ref "X4") (pin "P$7") (pinfunction "G_P$7") (pintype "bidirectional"))
      (node (ref "X4") (pin "P$8") (pinfunction "G_P$8") (pintype "bidirectional"))
      (node (ref "X5") (pin "P$6") (pinfunction "6_P$6") (pintype "passive"))
      (node (ref "X5") (pin "P$7") (pinfunction "G_P$7") (pintype "bidirectional"))
      (node (ref "X5") (pin "P$8") (pinfunction "G_P$8") (pintype "bidirectional"))
      (node (ref "X6") (pin "A1") (pinfunction "GND_1_A1") (pintype "bidirectional"))
      (node (ref "X6") (pin "A12") (pinfunction "GND_2_A12") (pintype "bidirectional"))
      (node (ref "X6") (pin "MH1") (pinfunction "MH1_MH1") (pintype "bidirectional"))
      (node (ref "X6") (pin "MH2") (pinfunction "MH2_MH2") (pintype "bidirectional"))
      (node (ref "X6") (pin "MH3") (pinfunction "MH3_MH3") (pintype "bidirectional"))
      (node (ref "X6") (pin "MH4") (pinfunction "MH4_MH4") (pintype "bidirectional"))
      (node (ref "X7") (pin "P$2") (pinfunction "P$2_P$2") (pintype "bidirectional"))
      (node (ref "X8") (pin "P$6") (pinfunction "6_P$6") (pintype "passive"))
      (node (ref "X8") (pin "P$7") (pinfunction "G_P$7") (pintype "bidirectional"))
      (node (ref "X8") (pin "P$8") (pinfunction "G_P$8") (pintype "bidirectional"))
      (node (ref "X9") (pin "1") (pinfunction "4_1") (pintype "bidirectional"))
      (node (ref "X9") (pin "7") (pinfunction "2_7") (pintype "bidirectional"))
      (node (ref "X9") (pin "8") (pinfunction "3_8") (pintype "bidirectional"))
      (node (ref "XT1") (pin "2") (pinfunction "GND_2") (pintype "power_in"))
      (node (ref "XT2") (pin "2") (pinfunction "GND_1_2") (pintype "bidirectional"))
      (node (ref "XT2") (pin "4") (pinfunction "GND_2_4") (pintype "bidirectional"))
    )
    (net (code "22") (name "IC1_TCK") (class "Default")
      (node (ref "RN6") (pin "2") (pinfunction "1_2") (pintype "passive"))
      (node (ref "X9") (pin "4") (pinfunction "7_4") (pintype "bidirectional"))
    )
    (net (code "23") (name "IC1_TDI") (class "Default")
      (node (ref "RN6") (pin "3") (pinfunction "1_3") (pintype "passive"))
      (node (ref "X9") (pin "3") (pinfunction "6_3") (pintype "bidirectional"))
    )
    (net (code "24") (name "IC1_TDO") (class "Default")
      (node (ref "RN6") (pin "4") (pinfunction "1_4") (pintype "passive"))
      (node (ref "X9") (pin "6") (pinfunction "5_6") (pintype "bidirectional"))
    )
    (net (code "25") (name "IC1_TMS") (class "Default")
      (node (ref "RN6") (pin "1") (pinfunction "1_1") (pintype "passive"))
      (node (ref "X9") (pin "5") (pinfunction "8_5") (pintype "bidirectional"))
    )
    (net (code "26") (name "IC2_AN1") (class "Default")
      (node (ref "IC2") (pin "9") (pinfunction "PA4_9") (pintype "bidirectional"))
      (node (ref "R5") (pin "2") (pinfunction "2_2") (pintype "passive"))
      (node (ref "TP3") (pin "TP") (pinfunction "TP_TP") (pintype "input"))
    )
    (net (code "27") (name "IC2_AN2") (class "Default")
      (node (ref "IC2") (pin "10") (pinfunction "PA5_10") (pintype "bidirectional"))
      (node (ref "R7") (pin "2") (pinfunction "2_2") (pintype "passive"))
      (node (ref "TP8") (pin "TP") (pinfunction "TP_TP") (pintype "input"))
    )
    (net (code "28") (name "IC2_AN3") (class "Default")
      (node (ref "IC2") (pin "11") (pinfunction "PA6_11") (pintype "bidirectional"))
      (node (ref "R9") (pin "2") (pinfunction "2_2") (pintype "passive"))
      (node (ref "TP7") (pin "TP") (pinfunction "TP_TP") (pintype "input"))
    )
    (net (code "29") (name "IC2_RST") (class "Default")
      (node (ref "C23") (pin "2") (pinfunction "2_2") (pintype "passive"))
      (node (ref "IC2") (pin "4") (pinfunction "PG10-NRST_4") (pintype "bidirectional"))
      (node (ref "R32") (pin "1") (pinfunction "1_1") (pintype "passive"))
    )
    (net (code "30") (name "IC2_RX") (class "Default")
      (node (ref "D1") (pin "1") (pinfunction "A_1") (pintype "passive"))
      (node (ref "R24") (pin "2") (pinfunction "2_2") (pintype "passive"))
      (node (ref "X1") (pin "P$3") (pinfunction "3_P$3") (pintype "passive"))
    )
    (net (code "31") (name "IC2_TX") (class "Default")
      (node (ref "D2") (pin "1") (pinfunction "A_1") (pintype "passive"))
      (node (ref "R23") (pin "2") (pinfunction "2_2") (pintype "passive"))
      (node (ref "X1") (pin "P$2") (pinfunction "2_P$2") (pintype "passive"))
    )
    (net (code "32") (name "Net-(D3-PadA)") (class "Default")
      (node (ref "D3") (pin "A") (pinfunction "A_A") (pintype "passive"))
      (node (ref "F1") (pin "2") (pinfunction "2_2") (pintype "passive"))
      (node (ref "FB1") (pin "1") (pinfunction "1_1") (pintype "passive"))
      (node (ref "FB2") (pin "1") (pinfunction "1_1") (pintype "passive"))
    )
    (net (code "33") (name "Net-(D3-PadC)") (class "Default")
      (node (ref "D3") (pin "C") (pinfunction "C_C") (pintype "passive"))
      (node (ref "R6") (pin "2") (pinfunction "2_2") (pintype "passive"))
    )
    (net (code "34") (name "Net-(D10-PadC)") (class "Default")
      (node (ref "D10") (pin "C") (pinfunction "C_C") (pintype "passive"))
      (node (ref "R17") (pin "2") (pinfunction "2_2") (pintype "passive"))
    )
    (net (code "35") (name "Net-(D11-PadC)") (class "Default")
      (node (ref "D11") (pin "C") (pinfunction "C_C") (pintype "passive"))
      (node (ref "R18") (pin "2") (pinfunction "2_2") (pintype "passive"))
    )
    (net (code "36") (name "Net-(IC1-3)") (class "Default")
      (node (ref "IC1") (pin "P$3") (pinfunction "3_P$3") (pintype "bidirectional"))
      (node (ref "R19") (pin "1") (pinfunction "1_1") (pintype "passive"))
    )
    (net (code "37") (name "Net-(IC1-4)") (class "Default")
      (node (ref "IC1") (pin "P$4") (pinfunction "4_P$4") (pintype "bidirectional"))
      (node (ref "R20") (pin "1") (pinfunction "1_1") (pintype "passive"))
    )
    (net (code "38") (name "Net-(IC1-5_TMS)") (class "Default")
      (node (ref "IC1") (pin "P$5") (pinfunction "5_TMS_P$5") (pintype "bidirectional"))
      (node (ref "RN6") (pin "8") (pinfunction "2_8") (pintype "passive"))
    )
    (net (code "39") (name "Net-(IC1-6_TCK)") (class "Default")
      (node (ref "IC1") (pin "P$6") (pinfunction "6_TCK_P$6") (pintype "bidirectional"))
      (node (ref "RN6") (pin "7") (pinfunction "2_7") (pintype "passive"))
    )
    (net (code "40") (name "Net-(IC1-7_TDI)") (class "Default")
      (node (ref "IC1") (pin "P$7") (pinfunction "7_TDI_P$7") (pintype "bidirectional"))
      (node (ref "RN6") (pin "6") (pinfunction "2_6") (pintype "passive"))
    )
    (net (code "41") (name "Net-(IC1-8_TDO)") (class "Default")
      (node (ref "IC1") (pin "P$8") (pinfunction "8_TDO_P$8") (pintype "bidirectional"))
      (node (ref "RN6") (pin "5") (pinfunction "2_5") (pintype "passive"))
    )
    (net (code "42") (name "Net-(IC1-9_RECONFIG_N)") (class "Default")
      (node (ref "IC1") (pin "P$9") (pinfunction "9_RECONFIG_N_P$9") (pintype "bidirectional"))
      (node (ref "R34") (pin "1") (pinfunction "1_1") (pintype "passive"))
    )
    (net (code "43") (name "Net-(IC1-25)") (class "Default")
      (node (ref "IC1") (pin "P$25") (pinfunction "25_P$25") (pintype "bidirectional"))
      (node (ref "RN3") (pin "8") (pinfunction "2_8") (pintype "passive"))
    )
    (net (code "44") (name "Net-(IC1-26)") (class "Default")
      (node (ref "IC1") (pin "P$26") (pinfunction "26_P$26") (pintype "bidirectional"))
      (node (ref "RN3") (pin "7") (pinfunction "2_7") (pintype "passive"))
    )
    (net (code "45") (name "Net-(IC1-27)") (class "Default")
      (node (ref "IC1") (pin "P$27") (pinfunction "27_P$27") (pintype "bidirectional"))
      (node (ref "RN3") (pin "6") (pinfunction "2_6") (pintype "passive"))
    )
    (net (code "46") (name "Net-(IC1-28)") (class "Default")
      (node (ref "IC1") (pin "P$28") (pinfunction "28_P$28") (pintype "bidirectional"))
      (node (ref "RN3") (pin "5") (pinfunction "2_5") (pintype "passive"))
    )
    (net (code "47") (name "Net-(IC1-30)") (class "Default")
      (node (ref "IC1") (pin "P$30") (pinfunction "30_P$30") (pintype "bidirectional"))
      (node (ref "RN4") (pin "8") (pinfunction "2_8") (pintype "passive"))
    )
    (net (code "48") (name "Net-(IC1-31)") (class "Default")
      (node (ref "IC1") (pin "P$31") (pinfunction "31_P$31") (pintype "bidirectional"))
      (node (ref "RN4") (pin "7") (pinfunction "2_7") (pintype "passive"))
    )
    (net (code "49") (name "Net-(IC1-32)") (class "Default")
      (node (ref "IC1") (pin "P$32") (pinfunction "32_P$32") (pintype "bidirectional"))
      (node (ref "RN4") (pin "6") (pinfunction "2_6") (pintype "passive"))
    )
    (net (code "50") (name "Net-(IC1-33)") (class "Default")
      (node (ref "IC1") (pin "P$33") (pinfunction "33_P$33") (pintype "bidirectional"))
      (node (ref "RN4") (pin "5") (pinfunction "2_5") (pintype "passive"))
    )
    (net (code "51") (name "Net-(IC1-39)") (class "Default")
      (node (ref "IC1") (pin "P$39") (pinfunction "39_P$39") (pintype "bidirectional"))
      (node (ref "RN5") (pin "8") (pinfunction "2_8") (pintype "passive"))
    )
    (net (code "52") (name "Net-(IC1-40)") (class "Default")
      (node (ref "IC1") (pin "P$40") (pinfunction "40_P$40") (pintype "bidirectional"))
      (node (ref "RN5") (pin "7") (pinfunction "2_7") (pintype "passive"))
    )
    (net (code "53") (name "Net-(IC1-41)") (class "Default")
      (node (ref "IC1") (pin "P$41") (pinfunction "41_P$41") (pintype "bidirectional"))
      (node (ref "RN5") (pin "6") (pinfunction "2_6") (pintype "passive"))
    )
    (net (code "54") (name "Net-(IC1-42)") (class "Default")
      (node (ref "IC1") (pin "P$42") (pinfunction "42_P$42") (pintype "bidirectional"))
      (node (ref "RN5") (pin "5") (pinfunction "2_5") (pintype "passive"))
    )
    (net (code "55") (name "Net-(IC2-PA0)") (class "Default")
      (node (ref "IC2") (pin "5") (pinfunction "PA0_5") (pintype "bidirectional"))
      (node (ref "RN1") (pin "8") (pinfunction "2_8") (pintype "passive"))
    )
    (net (code "56") (name "Net-(IC2-PA1)") (class "Default")
      (node (ref "IC2") (pin "6") (pinfunction "PA1_6") (pintype "bidirectional"))
      (node (ref "RN1") (pin "7") (pinfunction "2_7") (pintype "passive"))
    )
    (net (code "57") (name "Net-(IC2-PA2)") (class "Default")
      (node (ref "IC2") (pin "7") (pinfunction "PA2_7") (pintype "bidirectional"))
      (node (ref "RN1") (pin "6") (pinfunction "2_6") (pintype "passive"))
    )
    (net (code "58") (name "Net-(IC2-PA3)") (class "Default")
      (node (ref "IC2") (pin "8") (pinfunction "PA3_8") (pintype "bidirectional"))
      (node (ref "RN1") (pin "5") (pinfunction "2_5") (pintype "passive"))
    )
    (net (code "59") (name "Net-(IC2-PA8)") (class "Default")
      (node (ref "IC2") (pin "18") (pinfunction "PA8_18") (pintype "bidirectional"))
      (node (ref "RN8") (pin "6") (pinfunction "2_6") (pintype "passive"))
    )
    (net (code "60") (name "Net-(IC2-PA9)") (class "Default")
      (node (ref "IC2") (pin "19") (pinfunction "PA9_19") (pintype "bidirectional"))
      (node (ref "RN8") (pin "7") (pinfunction "2_7") (pintype "passive"))
    )
    (net (code "61") (name "Net-(IC2-PA10)") (class "Default")
      (node (ref "IC2") (pin "20") (pinfunction "PA10_20") (pintype "bidirectional"))
      (node (ref "RN8") (pin "8") (pinfunction "2_8") (pintype "passive"))
    )
    (net (code "62") (name "Net-(IC2-PA13)") (class "Default")
      (node (ref "IC2") (pin "23") (pinfunction "PA13_23") (pintype "bidirectional"))
      (node (ref "R4") (pin "2") (pinfunction "2_2") (pintype "passive"))
    )
    (net (code "63") (name "Net-(IC2-PA14)") (class "Default")
      (node (ref "IC2") (pin "24") (pinfunction "PA14_24") (pintype "bidirectional"))
      (node (ref "R3") (pin "2") (pinfunction "2_2") (pintype "passive"))
    )
    (net (code "64") (name "Net-(IC2-PA15)") (class "Default")
      (node (ref "C26") (pin "2") (pinfunction "2_2") (pintype "passive"))
      (node (ref "IC2") (pin "25") (pinfunction "PA15_25") (pintype "bidirectional"))
      (node (ref "RN2") (pin "4") (pinfunction "1_4") (pintype "passive"))
    )
    (net (code "65") (name "Net-(IC2-PB3)") (class "Default")
      (node (ref "IC2") (pin "26") (pinfunction "PB3_26") (pintype "bidirectional"))
      (node (ref "R23") (pin "1") (pinfunction "1_1") (pintype "passive"))
    )
    (net (code "66") (name "Net-(IC2-PB4)") (class "Default")
      (node (ref "IC2") (pin "27") (pinfunction "PB4_27") (pintype "bidirectional"))
      (node (ref "R24") (pin "1") (pinfunction "1_1") (pintype "passive"))
    )
    (net (code "67") (name "Net-(IC2-PB5)") (class "Default")
      (node (ref "C25") (pin "2") (pinfunction "2_2") (pintype "passive"))
      (node (ref "IC2") (pin "28") (pinfunction "PB5_28") (pintype "bidirectional"))
      (node (ref "RN2") (pin "3") (pinfunction "1_3") (pintype "passive"))
    )
    (net (code "68") (name "Net-(IC2-PB6)") (class "Default")
      (node (ref "C24") (pin "2") (pinfunction "2_2") (pintype "passive"))
      (node (ref "IC2") (pin "29") (pinfunction "PB6_29") (pintype "bidirectional"))
      (node (ref "RN2") (pin "2") (pinfunction "1_2") (pintype "passive"))
    )
    (net (code "69") (name "Net-(IC2-PB7)") (class "Default")
      (node (ref "C1") (pin "2") (pinfunction "2_2") (pintype "passive"))
      (node (ref "IC2") (pin "30") (pinfunction "PB7_30") (pintype "bidirectional"))
      (node (ref "RN2") (pin "1") (pinfunction "1_1") (pintype "passive"))
    )
    (net (code "70") (name "Net-(IC2-PB8-BOOT0)") (class "Default")
      (node (ref "IC2") (pin "31") (pinfunction "PB8-BOOT0_31") (pintype "bidirectional"))
      (node (ref "R22") (pin "2") (pinfunction "2_2") (pintype "passive"))
    )
    (net (code "71") (name "Net-(IC2-PF0-OSC_IN)") (class "Default")
      (node (ref "C4") (pin "1") (pinfunction "1_1") (pintype "passive"))
      (node (ref "IC2") (pin "2") (pinfunction "PF0-OSC_IN_2") (pintype "bidirectional"))
      (node (ref "XT2") (pin "1") (pinfunction "C_1_1") (pintype "bidirectional"))
    )
    (net (code "72") (name "Net-(IC2-PF1-OSC_OUT)") (class "Default")
      (node (ref "C5") (pin "1") (pinfunction "1_1") (pintype "passive"))
      (node (ref "IC2") (pin "3") (pinfunction "PF1-OSC_OUT_3") (pintype "bidirectional"))
      (node (ref "XT2") (pin "3") (pinfunction "C_2_3") (pintype "bidirectional"))
    )
    (net (code "73") (name "Net-(IC2-VDDA)") (class "Default")
      (node (ref "C2") (pin "1") (pinfunction "1_1") (pintype "passive"))
      (node (ref "FB5") (pin "2") (pinfunction "2_2") (pintype "passive"))
      (node (ref "IC2") (pin "15") (pinfunction "VDDA_15") (pintype "bidirectional"))
    )
    (net (code "74") (name "Net-(IC3-+IN)") (class "Default")
      (node (ref "C21") (pin "1") (pinfunction "1_1") (pintype "passive"))
      (node (ref "IC3") (pin "1") (pinfunction "+IN_1") (pintype "input"))
      (node (ref "R25") (pin "2") (pinfunction "2_2") (pintype "passive"))
      (node (ref "R26") (pin "1") (pinfunction "1_1") (pintype "passive"))
    )
    (net (code "75") (name "Net-(IC3--IN)") (class "Default")
      (node (ref "IC3") (pin "3") (pinfunction "-IN_3") (pintype "input"))
      (node (ref "IC3") (pin "4") (pinfunction "OUT_4") (pintype "output"))
      (node (ref "R5") (pin "1") (pinfunction "1_1") (pintype "passive"))
    )
    (net (code "76") (name "Net-(IC3-V+)") (class "Default")
      (node (ref "C6") (pin "1") (pinfunction "1_1") (pintype "passive"))
      (node (ref "FB6") (pin "1") (pinfunction "1_1") (pintype "passive"))
      (node (ref "IC3") (pin "5") (pinfunction "V+_5") (pintype "power_in"))
      (node (ref "R25") (pin "1") (pinfunction "1_1") (pintype "passive"))
    )
    (net (code "77") (name "Net-(IC4-BST)") (class "Default")
      (node (ref "C11") (pin "1") (pinfunction "1_1") (pintype "passive"))
      (node (ref "IC4") (pin "1") (pinfunction "BST_1") (pintype "bidirectional"))
    )
    (net (code "78") (name "Net-(IC4-EN)") (class "Default")
      (node (ref "IC4") (pin "4") (pinfunction "EN_4") (pintype "bidirectional"))
      (node (ref "R12") (pin "1") (pinfunction "1_1") (pintype "passive"))
    )
    (net (code "79") (name "Net-(IC4-FB)") (class "Default")
      (node (ref "C12") (pin "2") (pinfunction "2_2") (pintype "passive"))
      (node (ref "IC4") (pin "3") (pinfunction "FB_3") (pintype "bidirectional"))
      (node (ref "R10") (pin "1") (pinfunction "1_1") (pintype "passive"))
      (node (ref "R11") (pin "2") (pinfunction "2_2") (pintype "passive"))
    )
    (net (code "80") (name "Net-(IC4-IN)") (class "Default")
      (node (ref "C15") (pin "1") (pinfunction "1_1") (pintype "passive"))
      (node (ref "FB1") (pin "2") (pinfunction "2_2") (pintype "passive"))
      (node (ref "IC4") (pin "5") (pinfunction "IN_5") (pintype "bidirectional"))
      (node (ref "R12") (pin "2") (pinfunction "2_2") (pintype "passive"))
    )
    (net (code "81") (name "Net-(IC4-SW)") (class "Default")
      (node (ref "C11") (pin "2") (pinfunction "2_2") (pintype "passive"))
      (node (ref "IC4") (pin "6") (pinfunction "SW_6") (pintype "bidirectional"))
      (node (ref "L5") (pin "P$1") (pinfunction "1_P$1") (pintype "passive"))
    )
    (net (code "82") (name "Net-(IC5-BST)") (class "Default")
      (node (ref "C14") (pin "1") (pinfunction "1_1") (pintype "passive"))
      (node (ref "IC5") (pin "1") (pinfunction "BST_1") (pintype "bidirectional"))
    )
    (net (code "83") (name "Net-(IC5-EN)") (class "Default")
      (node (ref "IC5") (pin "4") (pinfunction "EN_4") (pintype "bidirectional"))
      (node (ref "R15") (pin "1") (pinfunction "1_1") (pintype "passive"))
    )
    (net (code "84") (name "Net-(IC5-FB)") (class "Default")
      (node (ref "C17") (pin "2") (pinfunction "2_2") (pintype "passive"))
      (node (ref "IC5") (pin "3") (pinfunction "FB_3") (pintype "bidirectional"))
      (node (ref "R13") (pin "1") (pinfunction "1_1") (pintype "passive"))
      (node (ref "R14") (pin "2") (pinfunction "2_2") (pintype "passive"))
    )
    (net (code "85") (name "Net-(IC5-IN)") (class "Default")
      (node (ref "C19") (pin "1") (pinfunction "1_1") (pintype "passive"))
      (node (ref "FB2") (pin "2") (pinfunction "2_2") (pintype "passive"))
      (node (ref "IC5") (pin "5") (pinfunction "IN_5") (pintype "bidirectional"))
      (node (ref "R15") (pin "2") (pinfunction "2_2") (pintype "passive"))
    )
    (net (code "86") (name "Net-(IC5-SW)") (class "Default")
      (node (ref "C14") (pin "2") (pinfunction "2_2") (pintype "passive"))
      (node (ref "IC5") (pin "6") (pinfunction "SW_6") (pintype "bidirectional"))
      (node (ref "L4") (pin "P$1") (pinfunction "1_P$1") (pintype "passive"))
    )
    (net (code "87") (name "Net-(IC6-+IN)") (class "Default")
      (node (ref "C10") (pin "1") (pinfunction "1_1") (pintype "passive"))
      (node (ref "IC6") (pin "1") (pinfunction "+IN_1") (pintype "input"))
      (node (ref "R8") (pin "2") (pinfunction "2_2") (pintype "passive"))
    )
    (net (code "88") (name "Net-(IC6--IN)") (class "Default")
      (node (ref "IC6") (pin "3") (pinfunction "-IN_3") (pintype "input"))
      (node (ref "IC6") (pin "4") (pinfunction "OUT_4") (pintype "output"))
      (node (ref "R7") (pin "1") (pinfunction "1_1") (pintype "passive"))
    )
    (net (code "89") (name "Net-(IC6-V+)") (class "Default")
      (node (ref "C7") (pin "1") (pinfunction "1_1") (pintype "passive"))
      (node (ref "FB7") (pin "1") (pinfunction "1_1") (pintype "passive"))
      (node (ref "IC6") (pin "5") (pinfunction "V+_5") (pintype "power_in"))
    )
    (net (code "90") (name "Net-(IC7-+IN)") (class "Default")
      (node (ref "C9") (pin "1") (pinfunction "1_1") (pintype "passive"))
      (node (ref "IC7") (pin "1") (pinfunction "+IN_1") (pintype "input"))
      (node (ref "R16") (pin "2") (pinfunction "2_2") (pintype "passive"))
    )
    (net (code "91") (name "Net-(IC7--IN)") (class "Default")
      (node (ref "IC7") (pin "3") (pinfunction "-IN_3") (pintype "input"))
      (node (ref "IC7") (pin "4") (pinfunction "OUT_4") (pintype "output"))
      (node (ref "R9") (pin "1") (pinfunction "1_1") (pintype "passive"))
    )
    (net (code "92") (name "Net-(IC7-V+)") (class "Default")
      (node (ref "C8") (pin "1") (pinfunction "1_1") (pintype "passive"))
      (node (ref "FB8") (pin "1") (pinfunction "1_1") (pintype "passive"))
      (node (ref "IC7") (pin "5") (pinfunction "V+_5") (pintype "power_in"))
    )
    (net (code "93") (name "Net-(IC8-CLK)") (class "Default")
      (node (ref "IC8") (pin "6") (pinfunction "CLK_6") (pintype "bidirectional"))
      (node (ref "RN7") (pin "2") (pinfunction "1_2") (pintype "passive"))
    )
    (net (code "94") (name "Net-(IC8-DI_(IO0))") (class "Default")
      (node (ref "IC8") (pin "5") (pinfunction "DI_(IO0)_5") (pintype "bidirectional"))
      (node (ref "RN7") (pin "1") (pinfunction "1_1") (pintype "passive"))
    )
    (net (code "95") (name "Net-(IC8-DO_(IO1))") (class "Default")
      (node (ref "IC8") (pin "2") (pinfunction "DO_(IO1)_2") (pintype "bidirectional"))
      (node (ref "RN7") (pin "3") (pinfunction "1_3") (pintype "passive"))
    )
    (net (code "96") (name "Net-(IC8-~{CS})") (class "Default")
      (node (ref "IC8") (pin "1") (pinfunction "~{CS}_1") (pintype "bidirectional"))
      (node (ref "RN7") (pin "4") (pinfunction "1_4") (pintype "passive"))
    )
    (net (code "97") (name "Net-(IC8-~{HOLD_OR_}{slash}RESET_(IO3))") (class "Default")
      (node (ref "IC8") (pin "7") (pinfunction "~{HOLD_OR_}/RESET_(IO3)_7") (pintype "bidirectional"))
      (node (ref "R36") (pin "2") (pinfunction "2_2") (pintype "passive"))
    )
    (net (code "98") (name "Net-(IC8-~{WP_(IO2}))") (class "Default")
      (node (ref "IC8") (pin "3") (pinfunction "~{WP_(IO2})_3") (pintype "bidirectional"))
      (node (ref "R35") (pin "2") (pinfunction "2_2") (pintype "passive"))
    )
    (net (code "99") (name "Net-(L4-4)") (class "Default")
      (node (ref "C17") (pin "1") (pinfunction "1_1") (pintype "passive"))
      (node (ref "C18") (pin "1") (pinfunction "1_1") (pintype "passive"))
      (node (ref "C20") (pin "1") (pinfunction "1_1") (pintype "passive"))
      (node (ref "FB4") (pin "1") (pinfunction "1_1") (pintype "passive"))
      (node (ref "L4") (pin "P$2") (pinfunction "4_P$2") (pintype "passive"))
      (node (ref "R13") (pin "2") (pinfunction "2_2") (pintype "passive"))
    )
    (net (code "100") (name "Net-(L5-4)") (class "Default")
      (node (ref "C12") (pin "1") (pinfunction "1_1") (pintype "passive"))
      (node (ref "C13") (pin "1") (pinfunction "1_1") (pintype "passive"))
      (node (ref "C16") (pin "1") (pinfunction "1_1") (pintype "passive"))
      (node (ref "FB3") (pin "1") (pinfunction "1_1") (pintype "passive"))
      (node (ref "L5") (pin "P$2") (pinfunction "4_P$2") (pintype "passive"))
      (node (ref "R10") (pin "2") (pinfunction "2_2") (pintype "passive"))
    )
    (net (code "101") (name "Net-(R32-Pad2)") (class "Default")
      (node (ref "R32") (pin "2") (pinfunction "2_2") (pintype "passive"))
      (node (ref "X7") (pin "P$5") (pinfunction "P$5_P$5") (pintype "bidirectional"))
    )
    (net (code "102") (name "Net-(X3-1)") (class "Default")
      (node (ref "R27") (pin "1") (pinfunction "1_1") (pintype "passive"))
      (node (ref "X3") (pin "P$1") (pinfunction "1_P$1") (pintype "passive"))
    )
    (net (code "103") (name "Net-(X4-1)") (class "Default")
      (node (ref "R28") (pin "1") (pinfunction "1_1") (pintype "passive"))
      (node (ref "X4") (pin "P$1") (pinfunction "1_P$1") (pintype "passive"))
    )
    (net (code "104") (name "Net-(X5-1)") (class "Default")
      (node (ref "R29") (pin "1") (pinfunction "1_1") (pintype "passive"))
      (node (ref "X5") (pin "P$1") (pinfunction "1_P$1") (pintype "passive"))
    )
    (net (code "105") (name "Net-(X6-DN1)") (class "Default")
      (node (ref "R31") (pin "2") (pinfunction "2_2") (pintype "passive"))
      (node (ref "X6") (pin "A7") (pinfunction "DN1_A7") (pintype "bidirectional"))
      (node (ref "X6") (pin "B7") (pinfunction "DN2_B7") (pintype "bidirectional"))
    )
    (net (code "106") (name "Net-(X6-DP1)") (class "Default")
      (node (ref "R30") (pin "2") (pinfunction "2_2") (pintype "passive"))
      (node (ref "X6") (pin "A6") (pinfunction "DP1_A6") (pintype "bidirectional"))
      (node (ref "X6") (pin "B6") (pinfunction "DP2_B6") (pintype "bidirectional"))
    )
    (net (code "107") (name "Net-(X6-VBUS_1)") (class "Default")
      (node (ref "D5") (pin "A") (pinfunction "A_A") (pintype "passive"))
      (node (ref "X6") (pin "A4") (pinfunction "VBUS_1_A4") (pintype "bidirectional"))
      (node (ref "X6") (pin "A9") (pinfunction "VBUS_2_A9") (pintype "bidirectional"))
    )
    (net (code "108") (name "Net-(XT1-E{slash}D)") (class "Default")
      (node (ref "R1") (pin "1") (pinfunction "1_1") (pintype "passive"))
      (node (ref "XT1") (pin "1") (pinfunction "E/D_1") (pintype "input"))
    )
    (net (code "109") (name "Net-(XT1-OUT)") (class "Default")
      (node (ref "R2") (pin "2") (pinfunction "2_2") (pintype "passive"))
      (node (ref "XT1") (pin "3") (pinfunction "OUT_3") (pintype "output"))
    )
    (net (code "110") (name "PWM1") (class "Default")
      (node (ref "IC1") (pin "P$49") (pinfunction "49_P$49") (pintype "bidirectional"))
      (node (ref "RN8") (pin "1") (pinfunction "1_1") (pintype "passive"))
    )
    (net (code "111") (name "PWM2") (class "Default")
      (node (ref "IC1") (pin "P$48") (pinfunction "48_P$48") (pintype "bidirectional"))
      (node (ref "RN8") (pin "2") (pinfunction "1_2") (pintype "passive"))
    )
    (net (code "112") (name "PWM3") (class "Default")
      (node (ref "IC1") (pin "P$47") (pinfunction "47_P$47") (pintype "bidirectional"))
      (node (ref "RN8") (pin "3") (pinfunction "1_3") (pintype "passive"))
    )
    (net (code "113") (name "REL_RX") (class "Default")
      (node (ref "R20") (pin "2") (pinfunction "2_2") (pintype "passive"))
      (node (ref "X11") (pin "P$6") (pinfunction "6_P$6") (pintype "passive"))
    )
    (net (code "114") (name "REL_TX") (class "Default")
      (node (ref "R19") (pin "2") (pinfunction "2_2") (pintype "passive"))
      (node (ref "X11") (pin "P$5") (pinfunction "5_P$5") (pintype "passive"))
    )
    (net (code "115") (name "SPI1_CLK") (class "Default")
      (node (ref "IC1") (pin "P$17") (pinfunction "17_P$17") (pintype "bidirectional"))
      (node (ref "RN7") (pin "8") (pinfunction "2_8") (pintype "passive"))
    )
    (net (code "116") (name "SPI1_CS") (class "Default")
      (node (ref "IC1") (pin "P$20") (pinfunction "20_P$20") (pintype "bidirectional"))
      (node (ref "RN7") (pin "5") (pinfunction "2_5") (pintype "passive"))
    )
    (net (code "117") (name "SPI1_DI") (class "Default")
      (node (ref "IC1") (pin "P$18") (pinfunction "18_P$18") (pintype "bidirectional"))
      (node (ref "RN7") (pin "7") (pinfunction "2_7") (pintype "passive"))
    )
    (net (code "118") (name "SPI1_DO") (class "Default")
      (node (ref "IC1") (pin "P$19") (pinfunction "19_P$19") (pintype "bidirectional"))
      (node (ref "RN7") (pin "6") (pinfunction "2_6") (pintype "passive"))
    )
    (net (code "119") (name "STAT_1") (class "Default")
      (node (ref "D11") (pin "A") (pinfunction "A_A") (pintype "passive"))
      (node (ref "IC1") (pin "P$38") (pinfunction "38_P$38") (pintype "bidirectional"))
    )
    (net (code "120") (name "STAT_2") (class "Default")
      (node (ref "D10") (pin "A") (pinfunction "A_A") (pintype "passive"))
      (node (ref "IC1") (pin "P$37") (pinfunction "37_P$37") (pintype "bidirectional"))
    )
    (net (code "121") (name "SWCK") (class "Default")
      (node (ref "R3") (pin "1") (pinfunction "1_1") (pintype "passive"))
      (node (ref "X7") (pin "P$4") (pinfunction "P$4_P$4") (pintype "bidirectional"))
    )
    (net (code "122") (name "SWD") (class "Default")
      (node (ref "R4") (pin "1") (pinfunction "1_1") (pintype "passive"))
      (node (ref "X7") (pin "P$3") (pinfunction "P$3_P$3") (pintype "bidirectional"))
    )
    (net (code "123") (name "TP1") (class "Default")
      (node (ref "RN2") (pin "8") (pinfunction "2_8") (pintype "passive"))
      (node (ref "X8") (pin "P$5") (pinfunction "5_P$5") (pintype "passive"))
    )
    (net (code "124") (name "TP2") (class "Default")
      (node (ref "RN2") (pin "7") (pinfunction "2_7") (pintype "passive"))
      (node (ref "X8") (pin "P$4") (pinfunction "4_P$4") (pintype "passive"))
    )
    (net (code "125") (name "TP3") (class "Default")
      (node (ref "RN2") (pin "6") (pinfunction "2_6") (pintype "passive"))
      (node (ref "X8") (pin "P$3") (pinfunction "3_P$3") (pintype "passive"))
    )
    (net (code "126") (name "TP4") (class "Default")
      (node (ref "RN2") (pin "5") (pinfunction "2_5") (pintype "passive"))
      (node (ref "X8") (pin "P$2") (pinfunction "2_P$2") (pintype "passive"))
    )
    (net (code "127") (name "USB_N") (class "Default")
      (node (ref "D4") (pin "1") (pinfunction "A_1") (pintype "passive"))
      (node (ref "IC2") (pin "21") (pinfunction "PA11_21") (pintype "bidirectional"))
      (node (ref "R31") (pin "1") (pinfunction "1_1") (pintype "passive"))
    )
    (net (code "128") (name "USB_P") (class "Default")
      (node (ref "D6") (pin "1") (pinfunction "A_1") (pintype "passive"))
      (node (ref "IC2") (pin "22") (pinfunction "PA12_22") (pintype "bidirectional"))
      (node (ref "R30") (pin "1") (pinfunction "1_1") (pintype "passive"))
    )
    (net (code "129") (name "VCC_1V2") (class "Default")
      (node (ref "C29") (pin "1") (pinfunction "1_1") (pintype "passive"))
      (node (ref "C30") (pin "1") (pinfunction "1_1") (pintype "passive"))
      (node (ref "C31") (pin "1") (pinfunction "1_1") (pintype "passive"))
      (node (ref "C35") (pin "1") (pinfunction "1_1") (pintype "passive"))
      (node (ref "FB4") (pin "2") (pinfunction "2_2") (pintype "passive"))
      (node (ref "IC1") (pin "P$1") (pinfunction "VCC_1_P$1") (pintype "bidirectional"))
      (node (ref "IC1") (pin "P$22") (pinfunction "VCC_2_P$22") (pintype "bidirectional"))
      (node (ref "IC1") (pin "P$45") (pinfunction "VCC_3_P$45") (pintype "bidirectional"))
      (node (ref "IC1") (pin "P$66") (pinfunction "VCC_4_P$66") (pintype "bidirectional"))
      (node (ref "TP2") (pin "TP") (pinfunction "TP_TP") (pintype "input"))
    )
    (net (code "130") (name "VCC_3V3") (class "Default")
      (node (ref "C27") (pin "1") (pinfunction "1_1") (pintype "passive"))
      (node (ref "C28") (pin "1") (pinfunction "1_1") (pintype "passive"))
      (node (ref "C3") (pin "1") (pinfunction "1_1") (pintype "passive"))
      (node (ref "C32") (pin "1") (pinfunction "1_1") (pintype "passive"))
      (node (ref "C33") (pin "1") (pinfunction "1_1") (pintype "passive"))
      (node (ref "C34") (pin "1") (pinfunction "1_1") (pintype "passive"))
      (node (ref "C39") (pin "1") (pinfunction "1_1") (pintype "passive"))
      (node (ref "C40") (pin "1") (pinfunction "1_1") (pintype "passive"))
      (node (ref "C41") (pin "1") (pinfunction "1_1") (pintype "passive"))
      (node (ref "C42") (pin "1") (pinfunction "1_1") (pintype "passive"))
      (node (ref "FB3") (pin "2") (pinfunction "2_2") (pintype "passive"))
      (node (ref "FB5") (pin "1") (pinfunction "1_1") (pintype "passive"))
      (node (ref "FB6") (pin "2") (pinfunction "2_2") (pintype "passive"))
      (node (ref "FB7") (pin "2") (pinfunction "2_2") (pintype "passive"))
      (node (ref "FB8") (pin "2") (pinfunction "2_2") (pintype "passive"))
      (node (ref "IC1") (pin "P$12") (pinfunction "VCCIO3_P$12") (pintype "bidirectional"))
      (node (ref "IC1") (pin "P$23") (pinfunction "VCCIO2_1_P$23") (pintype "bidirectional"))
      (node (ref "IC1") (pin "P$44") (pinfunction "VCCIO2_2_P$44") (pintype "bidirectional"))
      (node (ref "IC1") (pin "P$58") (pinfunction "VCCIO1_P$58") (pintype "bidirectional"))
      (node (ref "IC1") (pin "P$64") (pinfunction "VCCX_1_P$64") (pintype "bidirectional"))
      (node (ref "IC1") (pin "P$67") (pinfunction "VCCIO0_P$67") (pintype "bidirectional"))
      (node (ref "IC1") (pin "P$78") (pinfunction "VCCX_2_P$78") (pintype "bidirectional"))
      (node (ref "IC2") (pin "1") (pinfunction "VDD_1_1") (pintype "bidirectional"))
      (node (ref "IC2") (pin "17") (pinfunction "VDD_2_17") (pintype "bidirectional"))
      (node (ref "IC8") (pin "8") (pinfunction "VCC_8") (pintype "bidirectional"))
      (node (ref "R1") (pin "2") (pinfunction "2_2") (pintype "passive"))
      (node (ref "R34") (pin "2") (pinfunction "2_2") (pintype "passive"))
      (node (ref "R35") (pin "1") (pinfunction "1_1") (pintype "passive"))
      (node (ref "R36") (pin "1") (pinfunction "1_1") (pintype "passive"))
      (node (ref "TP1") (pin "TP") (pinfunction "TP_TP") (pintype "input"))
      (node (ref "X1") (pin "P$1") (pinfunction "1_P$1") (pintype "passive"))
      (node (ref "X7") (pin "P$1") (pinfunction "P$1_P$1") (pintype "bidirectional"))
      (node (ref "X8") (pin "P$1") (pinfunction "1_P$1") (pintype "passive"))
      (node (ref "X9") (pin "2") (pinfunction "1_2") (pintype "bidirectional"))
      (node (ref "XT1") (pin "4") (pinfunction "VCC_4") (pintype "power_in"))
    )
    (net (code "131") (name "VEX_12V") (class "Default")
      (node (ref "D5") (pin "C") (pinfunction "C_C") (pintype "passive"))
      (node (ref "F1") (pin "1") (pinfunction "1_1") (pintype "passive"))
      (node (ref "R27") (pin "2") (pinfunction "2_2") (pintype "passive"))
      (node (ref "R28") (pin "2") (pinfunction "2_2") (pintype "passive"))
      (node (ref "R29") (pin "2") (pinfunction "2_2") (pintype "passive"))
      (node (ref "X11") (pin "P$3") (pinfunction "3_P$3") (pintype "passive"))
      (node (ref "X11") (pin "P$4") (pinfunction "4_P$4") (pintype "passive"))
      (node (ref "X2") (pin "1") (pinfunction "1_1") (pintype "passive"))
      (node (ref "X2") (pin "2") (pinfunction "2_2") (pintype "passive"))
    )
    (net (code "132") (name "unconnected-(IC1-10_GCLKT_6-PadP$10)") (class "Default")
      (node (ref "IC1") (pin "P$10") (pinfunction "10_GCLKT_6_P$10") (pintype "bidirectional"))
    )
    (net (code "133") (name "unconnected-(IC1-11-PadP$11)") (class "Default")
      (node (ref "IC1") (pin "P$11") (pinfunction "11_P$11") (pintype "bidirectional"))
    )
    (net (code "134") (name "unconnected-(IC1-13-PadP$13)") (class "Default")
      (node (ref "IC1") (pin "P$13") (pinfunction "13_P$13") (pintype "bidirectional"))
    )
    (net (code "135") (name "unconnected-(IC1-14-PadP$14)") (class "Default")
      (node (ref "IC1") (pin "P$14") (pinfunction "14_P$14") (pintype "bidirectional"))
    )
    (net (code "136") (name "unconnected-(IC1-15-PadP$15)") (class "Default")
      (node (ref "IC1") (pin "P$15") (pinfunction "15_P$15") (pintype "bidirectional"))
    )
    (net (code "137") (name "unconnected-(IC1-16-PadP$16)") (class "Default")
      (node (ref "IC1") (pin "P$16") (pinfunction "16_P$16") (pintype "bidirectional"))
    )
    (net (code "138") (name "unconnected-(IC1-29-PadP$29)") (class "Default")
      (node (ref "IC1") (pin "P$29") (pinfunction "29_P$29") (pintype "bidirectional"))
    )
    (net (code "139") (name "unconnected-(IC1-34-PadP$34)") (class "Default")
      (node (ref "IC1") (pin "P$34") (pinfunction "34_P$34") (pintype "bidirectional"))
    )
    (net (code "140") (name "unconnected-(IC1-35_GCLKT_4-PadP$35)") (class "Default")
      (node (ref "IC1") (pin "P$35") (pinfunction "35_GCLKT_4_P$35") (pintype "bidirectional"))
    )
    (net (code "141") (name "unconnected-(IC1-36_GCLKC_4-PadP$36)") (class "Default")
      (node (ref "IC1") (pin "P$36") (pinfunction "36_GCLKC_4_P$36") (pintype "bidirectional"))
    )
    (net (code "142") (name "unconnected-(IC1-50-PadP$50)") (class "Default")
      (node (ref "IC1") (pin "P$50") (pinfunction "50_P$50") (pintype "bidirectional"))
    )
    (net (code "143") (name "unconnected-(IC1-51_GCLKC_3-PadP$51)") (class "Default")
      (node (ref "IC1") (pin "P$51") (pinfunction "51_GCLKC_3_P$51") (pintype "bidirectional"))
    )
    (net (code "144") (name "unconnected-(IC1-53-PadP$53)") (class "Default")
      (node (ref "IC1") (pin "P$53") (pinfunction "53_P$53") (pintype "bidirectional"))
    )
    (net (code "145") (name "unconnected-(IC1-54-PadP$54)") (class "Default")
      (node (ref "IC1") (pin "P$54") (pinfunction "54_P$54") (pintype "bidirectional"))
    )
    (net (code "146") (name "unconnected-(IC1-55-PadP$55)") (class "Default")
      (node (ref "IC1") (pin "P$55") (pinfunction "55_P$55") (pintype "bidirectional"))
    )
    (net (code "147") (name "unconnected-(IC1-56-PadP$56)") (class "Default")
      (node (ref "IC1") (pin "P$56") (pinfunction "56_P$56") (pintype "bidirectional"))
    )
    (net (code "148") (name "unconnected-(IC1-57-PadP$57)") (class "Default")
      (node (ref "IC1") (pin "P$57") (pinfunction "57_P$57") (pintype "bidirectional"))
    )
    (net (code "149") (name "unconnected-(IC1-59-PadP$59)") (class "Default")
      (node (ref "IC1") (pin "P$59") (pinfunction "59_P$59") (pintype "bidirectional"))
    )
    (net (code "150") (name "unconnected-(IC1-68-PadP$68)") (class "Default")
      (node (ref "IC1") (pin "P$68") (pinfunction "68_P$68") (pintype "bidirectional"))
    )
    (net (code "151") (name "unconnected-(IC1-69-PadP$69)") (class "Default")
      (node (ref "IC1") (pin "P$69") (pinfunction "69_P$69") (pintype "bidirectional"))
    )
    (net (code "152") (name "unconnected-(IC1-70-PadP$70)") (class "Default")
      (node (ref "IC1") (pin "P$70") (pinfunction "70_P$70") (pintype "bidirectional"))
    )
    (net (code "153") (name "unconnected-(IC1-71-PadP$71)") (class "Default")
      (node (ref "IC1") (pin "P$71") (pinfunction "71_P$71") (pintype "bidirectional"))
    )
    (net (code "154") (name "unconnected-(IC1-72-PadP$72)") (class "Default")
      (node (ref "IC1") (pin "P$72") (pinfunction "72_P$72") (pintype "bidirectional"))
    )
    (net (code "155") (name "unconnected-(IC1-73-PadP$73)") (class "Default")
      (node (ref "IC1") (pin "P$73") (pinfunction "73_P$73") (pintype "bidirectional"))
    )
    (net (code "156") (name "unconnected-(IC1-74-PadP$74)") (class "Default")
      (node (ref "IC1") (pin "P$74") (pinfunction "74_P$74") (pintype "bidirectional"))
    )
    (net (code "157") (name "unconnected-(IC1-75-PadP$75)") (class "Default")
      (node (ref "IC1") (pin "P$75") (pinfunction "75_P$75") (pintype "bidirectional"))
    )
    (net (code "158") (name "unconnected-(IC1-76-PadP$76)") (class "Default")
      (node (ref "IC1") (pin "P$76") (pinfunction "76_P$76") (pintype "bidirectional"))
    )
    (net (code "159") (name "unconnected-(IC1-77-PadP$77)") (class "Default")
      (node (ref "IC1") (pin "P$77") (pinfunction "77_P$77") (pintype "bidirectional"))
    )
    (net (code "160") (name "unconnected-(IC1-79-PadP$79)") (class "Default")
      (node (ref "IC1") (pin "P$79") (pinfunction "79_P$79") (pintype "bidirectional"))
    )
    (net (code "161") (name "unconnected-(IC1-80-PadP$80)") (class "Default")
      (node (ref "IC1") (pin "P$80") (pinfunction "80_P$80") (pintype "bidirectional"))
    )
    (net (code "162") (name "unconnected-(IC1-81-PadP$81)") (class "Default")
      (node (ref "IC1") (pin "P$81") (pinfunction "81_P$81") (pintype "bidirectional"))
    )
    (net (code "163") (name "unconnected-(IC1-82-PadP$82)") (class "Default")
      (node (ref "IC1") (pin "P$82") (pinfunction "82_P$82") (pintype "bidirectional"))
    )
    (net (code "164") (name "unconnected-(IC1-83-PadP$83)") (class "Default")
      (node (ref "IC1") (pin "P$83") (pinfunction "83_P$83") (pintype "bidirectional"))
    )
    (net (code "165") (name "unconnected-(IC1-84-PadP$84)") (class "Default")
      (node (ref "IC1") (pin "P$84") (pinfunction "84_P$84") (pintype "bidirectional"))
    )
    (net (code "166") (name "unconnected-(IC1-85-PadP$85)") (class "Default")
      (node (ref "IC1") (pin "P$85") (pinfunction "85_P$85") (pintype "bidirectional"))
    )
    (net (code "167") (name "unconnected-(IC1-86-PadP$86)") (class "Default")
      (node (ref "IC1") (pin "P$86") (pinfunction "86_P$86") (pintype "bidirectional"))
    )
    (net (code "168") (name "unconnected-(IC1-87-PadP$87)") (class "Default")
      (node (ref "IC1") (pin "P$87") (pinfunction "87_P$87") (pintype "bidirectional"))
    )
    (net (code "169") (name "unconnected-(IC1-88-PadP$88)") (class "Default")
      (node (ref "IC1") (pin "P$88") (pinfunction "88_P$88") (pintype "bidirectional"))
    )
    (net (code "170") (name "unconnected-(IC2-PA7-Pad12)") (class "Default")
      (node (ref "IC2") (pin "12") (pinfunction "PA7_12") (pintype "bidirectional"))
    )
    (net (code "171") (name "unconnected-(IC2-PB0-Pad13)") (class "Default")
      (node (ref "IC2") (pin "13") (pinfunction "PB0_13") (pintype "bidirectional"))
    )
    (net (code "172") (name "unconnected-(X6-CC1-PadA5)") (class "Default")
      (node (ref "X6") (pin "A5") (pinfunction "CC1_A5") (pintype "bidirectional"))
    )
    (net (code "173") (name "unconnected-(X6-CC2-PadB5)") (class "Default")
      (node (ref "X6") (pin "B5") (pinfunction "CC2_B5") (pintype "bidirectional"))
    )
    (net (code "174") (name "unconnected-(X6-SBU1-PadA8)") (class "Default")
      (node (ref "X6") (pin "A8") (pinfunction "SBU1_A8") (pintype "bidirectional"))
    )
    (net (code "175") (name "unconnected-(X6-SBU2-PadB8)") (class "Default")
      (node (ref "X6") (pin "B8") (pinfunction "SBU2_B8") (pintype "bidirectional"))
    )
  )
)
